# 1_P1.net
KiCad netlist of a schematic drawn in Altium Designer
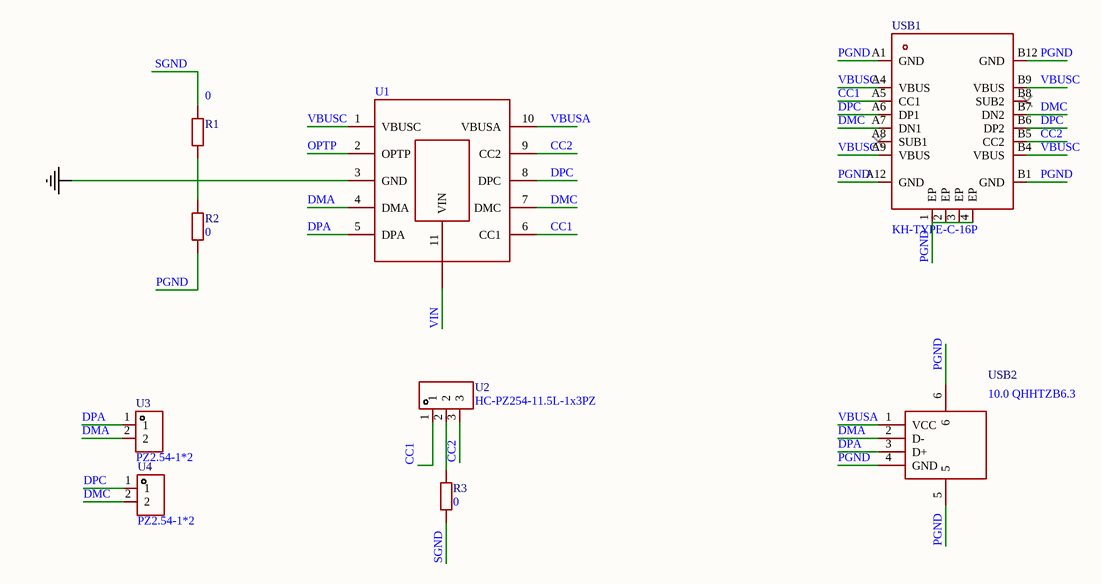
[diagram p0: 1_P1.schdoc]

(export (version "E")
  (design (tool "Eeschema 10.0.6"))
  (components
    (comp (ref "R1")
      (value "0")
      (footprint "R0603")
      (fields
        (field (name "MANUFACTURER") "UNI-ROYAL(厚声)")
        (field (name "MANUFACTURER PART") "0603WAF4700T5E")
        (field (name "TOLERANCE") "±1%")
      )
      (libsource (lib "altium-import") (part "root_1_R0603_"))
    )
    (comp (ref "R2")
      (value "0")
      (footprint "R0603")
      (fields
        (field (name "MANUFACTURER") "UNI-ROYAL(厚声)")
        (field (name "MANUFACTURER PART") "0603WAF4700T5E")
        (field (name "TOLERANCE") "±1%")
      )
      (libsource (lib "altium-import") (part "root_1_R0603_"))
    )
    (comp (ref "R3")
      (value "0")
      (footprint "R0603")
      (fields
        (field (name "MANUFACTURER") "UNI-ROYAL(厚声)")
        (field (name "MANUFACTURER PART") "0603WAF4700T5E")
        (field (name "TOLERANCE") "±1%")
      )
      (libsource (lib "altium-import") (part "root_3_R0603_"))
    )
    (comp (ref "U1")
      (value "~")
      (footprint "ESSOP-10_L4.9-W3.9-P1.00-LS6.0-BL-EP")
      (libsource (lib "altium-import") (part "root_0_OM5236_"))
    )
    (comp (ref "U2")
      (value "HC-PZ254-11.5L-1x3PZ")
      (footprint "HDR-TH_3P-P2.54-V-M")
      (fields (field (name "MANUFACTURER") "HC(虹成电子)"))
      (libsource (lib "altium-import") (part "root_1_HC-PZ254-11.5L-1x3PZ_"))
    )
    (comp (ref "U3")
      (value "PZ2.54-1*2")
      (footprint "HDR-TH_2P-P2.54-V-M-3")
      (fields (field (name "MANUFACTURER") "ZHOURI(洲日)"))
      (libsource (lib "altium-import") (part "root_0_PZ2.54-1*2_"))
    )
    (comp (ref "U4")
      (value "PZ2.54-1*2")
      (footprint "HDR-TH_2P-P2.54-V-M-3")
      (fields (field (name "MANUFACTURER") "ZHOURI(洲日)"))
      (libsource (lib "altium-import") (part "root_0_PZ2.54-1*2_"))
    )
    (comp (ref "USB1")
      (value "KH-TYPE-C-16P")
      (footprint "USB-C-SMD_KH-TYPE-C-16P")
      (fields (field (name "MANUFACTURER") "kinghelm(金航标)"))
      (libsource (lib "altium-import") (part "root_0_KH-TYPE-C-16P_"))
    )
    (comp (ref "USB2")
      (value "10.0 QHHTZB6.3")
      (footprint "USB-A-TH_10.0QHHTZB6.3")
      (fields (field (name "MANUFACTURER") "SHOU HAN(首韩)"))
      (libsource (lib "altium-import") (part "root_0_10.0 QHHTZB6.3_"))
    )
  )
  (nets
    (net (code "1") (name "/CC1") (class "Default")
      (node (ref "U1") (pin "6") (pinfunction "CC1_6") (pintype "passive"))
      (node (ref "U2") (pin "1") (pinfunction "1_1") (pintype "passive"))
      (node (ref "USB1") (pin "A5") (pinfunction "CC1_A5") (pintype "passive"))
    )
    (net (code "2") (name "/CC2") (class "Default")
      (node (ref "U1") (pin "9") (pinfunction "CC2_9") (pintype "passive"))
      (node (ref "U2") (pin "3") (pinfunction "3_3") (pintype "passive"))
      (node (ref "USB1") (pin "B5") (pinfunction "CC2_B5") (pintype "passive"))
    )
    (net (code "3") (name "/DMA") (class "Default")
      (node (ref "U1") (pin "4") (pinfunction "DMA_4") (pintype "passive"))
      (node (ref "U3") (pin "2") (pinfunction "2_2") (pintype "passive"))
      (node (ref "USB2") (pin "2") (pinfunction "D-_2") (pintype "passive"))
    )
    (net (code "4") (name "/DMC") (class "Default")
      (node (ref "U1") (pin "7") (pinfunction "DMC_7") (pintype "passive"))
      (node (ref "U4") (pin "2") (pinfunction "2_2") (pintype "passive"))
      (node (ref "USB1") (pin "A7") (pinfunction "DN1_A7") (pintype "passive"))
      (node (ref "USB1") (pin "B7") (pinfunction "DN2_B7") (pintype "passive"))
    )
    (net (code "5") (name "/DPA") (class "Default")
      (node (ref "U1") (pin "5") (pinfunction "DPA_5") (pintype "passive"))
      (node (ref "U3") (pin "1") (pinfunction "1_1") (pintype "passive"))
      (node (ref "USB2") (pin "3") (pinfunction "D+_3") (pintype "passive"))
    )
    (net (code "6") (name "/DPC") (class "Default")
      (node (ref "U1") (pin "8") (pinfunction "DPC_8") (pintype "passive"))
      (node (ref "U4") (pin "1") (pinfunction "1_1") (pintype "passive"))
      (node (ref "USB1") (pin "A6") (pinfunction "DP1_A6") (pintype "passive"))
      (node (ref "USB1") (pin "B6") (pinfunction "DP2_B6") (pintype "passive"))
    )
    (net (code "7") (name "/OPTP") (class "Default")
      (node (ref "U1") (pin "2") (pinfunction "OPTP_2") (pintype "passive"))
    )
    (net (code "8") (name "/PGND") (class "Default")
      (node (ref "R2") (pin "1") (pinfunction "1_1") (pintype "passive"))
      (node (ref "USB1") (pin "1") (pinfunction "EP_1") (pintype "passive"))
      (node (ref "USB1") (pin "2") (pinfunction "EP_2") (pintype "passive"))
      (node (ref "USB1") (pin "3") (pinfunction "EP_3") (pintype "passive"))
      (node (ref "USB1") (pin "4") (pinfunction "EP_4") (pintype "passive"))
      (node (ref "USB1") (pin "A1") (pinfunction "GND_A1") (pintype "passive"))
      (node (ref "USB1") (pin "A12") (pinfunction "GND_A12") (pintype "passive"))
      (node (ref "USB1") (pin "B1") (pinfunction "GND_B1") (pintype "passive"))
      (node (ref "USB1") (pin "B12") (pinfunction "GND_B12") (pintype "passive"))
      (node (ref "USB2") (pin "4") (pinfunction "GND_4") (pintype "passive"))
      (node (ref "USB2") (pin "5") (pinfunction "5_5") (pintype "passive"))
      (node (ref "USB2") (pin "6") (pinfunction "6_6") (pintype "passive"))
    )
    (net (code "9") (name "/SGND") (class "Default")
      (node (ref "R1") (pin "2") (pinfunction "2_2") (pintype "passive"))
      (node (ref "R3") (pin "2") (pinfunction "2_2") (pintype "passive"))
    )
    (net (code "10") (name "/VBUSA") (class "Default")
      (node (ref "U1") (pin "10") (pinfunction "VBUSA_10") (pintype "passive"))
      (node (ref "USB2") (pin "1") (pinfunction "VCC_1") (pintype "passive"))
    )
    (net (code "11") (name "/VBUSC") (class "Default")
      (node (ref "U1") (pin "1") (pinfunction "VBUSC_1") (pintype "passive"))
      (node (ref "USB1") (pin "A4") (pinfunction "VBUS_A4") (pintype "passive"))
      (node (ref "USB1") (pin "A9") (pinfunction "VBUS_A9") (pintype "passive"))
      (node (ref "USB1") (pin "B4") (pinfunction "VBUS_B4") (pintype "passive"))
      (node (ref "USB1") (pin "B9") (pinfunction "VBUS_B9") (pintype "passive"))
    )
    (net (code "12") (name "/VIN") (class "Default")
      (node (ref "U1") (pin "11") (pinfunction "VIN_11") (pintype "passive"))
    )
    (net (code "13") (name "GND") (class "Default")
      (node (ref "R1") (pin "1") (pinfunction "1_1") (pintype "passive"))
      (node (ref "R2") (pin "2") (pinfunction "2_2") (pintype "passive"))
      (node (ref "U1") (pin "3") (pinfunction "GND_3") (pintype "passive"))
    )
    (net (code "14") (name "Net-(R3-Pad1)") (class "Default")
      (node (ref "R3") (pin "1") (pinfunction "1_1") (pintype "passive"))
      (node (ref "U2") (pin "2") (pinfunction "2_2") (pintype "passive"))
    )
    (net (code "15") (name "unconnected-(USB1-SUB1-PadA8)") (class "Default")
      (node (ref "USB1") (pin "A8") (pinfunction "SUB1_A8") (pintype "passive+no_connect"))
    )
    (net (code "16") (name "unconnected-(USB1-SUB2-PadB8)") (class "Default")
      (node (ref "USB1") (pin "B8") (pinfunction "SUB2_B8") (pintype "passive+no_connect"))
    )
  )
)
